# Master.net
KiCad netlist of a schematic drawn in EAGLE
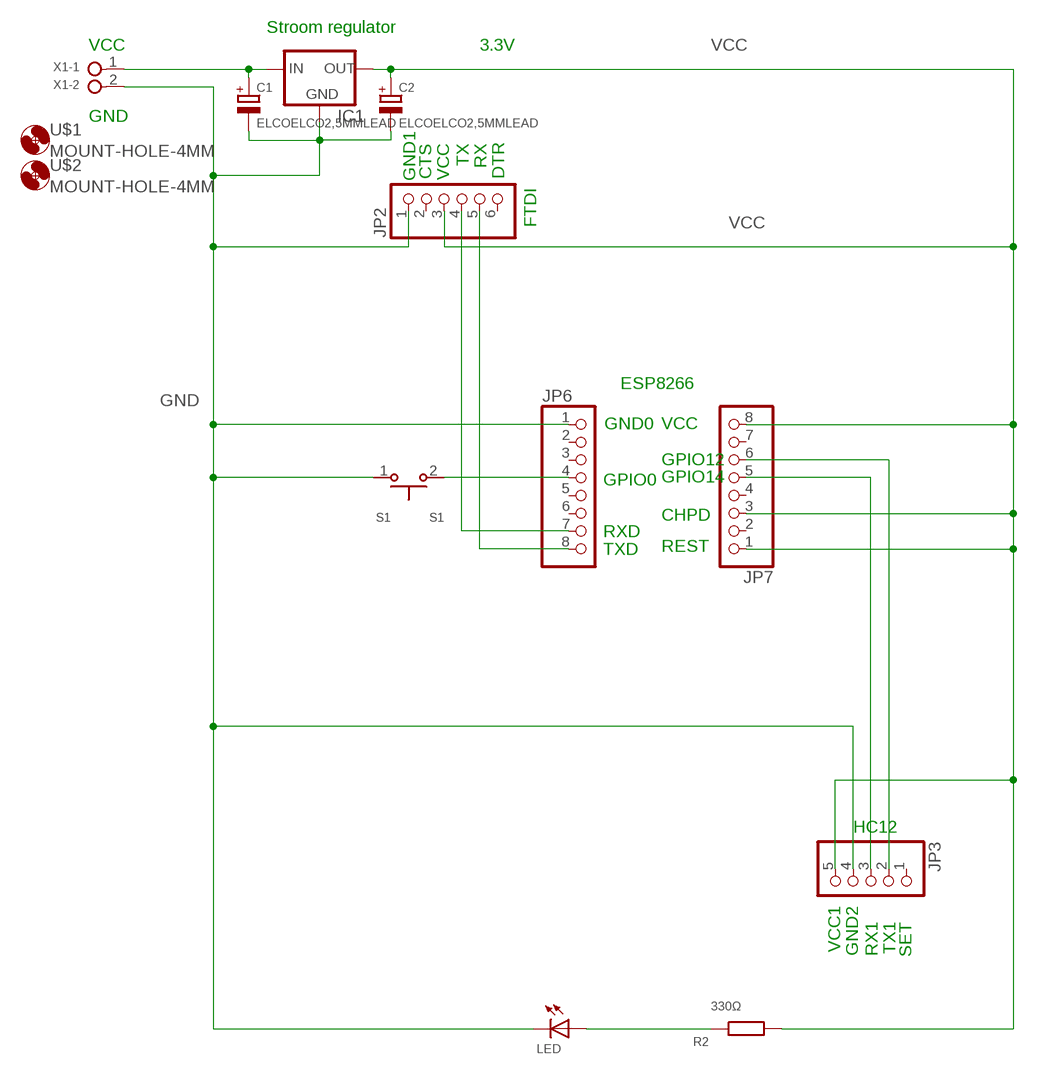
[diagram p0: schematic, sheet 1]

(export (version "E")
  (design (tool "Eeschema 10.0.6"))
  (components
    (comp (ref "C1")
      (value "ELCOELCO2,5MMLEAD")
      (footprint "eagle-import:ELCO-2.5MMLEAD")
      (libsource (lib "eagle-import") (part "ELCOELCO2,5MMLEAD"))
    )
    (comp (ref "C2")
      (value "ELCOELCO2,5MMLEAD")
      (footprint "eagle-import:ELCO-2.5MMLEAD")
      (libsource (lib "eagle-import") (part "ELCOELCO2,5MMLEAD"))
    )
    (comp (ref "IC1")
      (value "LM1117-TO220")
      (footprint "eagle-import:TO220V")
      (libsource (lib "eagle-import") (part "LM1117-TO220"))
    )
    (comp (ref "JP2")
      (value "PINHD-1X6")
      (footprint "eagle-import:1X06")
      (libsource (lib "eagle-import") (part "PINHD-1X6"))
    )
    (comp (ref "JP3")
      (value "PINHD-1X5")
      (footprint "eagle-import:1X05")
      (libsource (lib "eagle-import") (part "PINHD-1X5"))
    )
    (comp (ref "JP6")
      (value "PINHD-1X8")
      (footprint "eagle-import:1X08")
      (libsource (lib "eagle-import") (part "PINHD-1X8"))
    )
    (comp (ref "JP7")
      (value "PINHD-1X8")
      (footprint "eagle-import:1X08")
      (libsource (lib "eagle-import") (part "PINHD-1X8"))
    )
    (comp (ref "LED")
      (value "LED-SMD1206")
      (footprint "eagle-import:CHIPLED_1206")
      (libsource (lib "eagle-import") (part "LED-SMD1206"))
    )
    (comp (ref "R2")
      (value "330Ω")
      (footprint "eagle-import:R1206W")
      (libsource (lib "eagle-import") (part "RESISTOR-SMD-1206"))
    )
    (comp (ref "S1")
      (value "MICROSWITCH-B3U-1000P")
      (footprint "eagle-import:MICROSWITCH-B3U-1000P")
      (libsource (lib "eagle-import") (part "MICROSWITCH-B3U-1000P"))
    )
    (comp (ref "U$1")
      (value "MOUNT-HOLE-4MM")
      (footprint "eagle-import:4,0")
      (libsource (lib "eagle-import") (part "MOUNT-HOLE-4MM"))
    )
    (comp (ref "U$2")
      (value "MOUNT-HOLE-4MM")
      (footprint "eagle-import:4,0")
      (libsource (lib "eagle-import") (part "MOUNT-HOLE-4MM"))
    )
    (comp (ref "X1")
      (value "TERMINAL-5MM-2POLE")
      (footprint "eagle-import:W237-132")
      (libsource (lib "eagle-import") (part "TERMINAL-5MM-2POLE"))
    )
  )
  (nets
    (net (code "1") (name "/GND") (class "Default")
      (node (ref "C1") (pin "-") (pinfunction "-_-") (pintype "passive"))
      (node (ref "C2") (pin "-") (pinfunction "-_-") (pintype "passive"))
      (node (ref "IC1") (pin "1") (pinfunction "GND_1") (pintype "passive"))
      (node (ref "JP2") (pin "1") (pinfunction "1_1") (pintype "passive"))
      (node (ref "JP3") (pin "4") (pinfunction "4_4") (pintype "passive"))
      (node (ref "JP6") (pin "1") (pinfunction "1_1") (pintype "passive"))
      (node (ref "LED") (pin "C") (pinfunction "C_C") (pintype "passive"))
      (node (ref "S1") (pin "1") (pinfunction "P$1_1") (pintype "bidirectional"))
      (node (ref "X1") (pin "2") (pinfunction "P$2_2") (pintype "passive"))
    )
    (net (code "2") (name "/VCC") (class "Default")
      (node (ref "C2") (pin "+") (pinfunction "+_+") (pintype "passive"))
      (node (ref "IC1") (pin "2") (pinfunction "OUT_2") (pintype "passive"))
      (node (ref "JP2") (pin "3") (pinfunction "3_3") (pintype "passive"))
      (node (ref "JP3") (pin "5") (pinfunction "5_5") (pintype "passive"))
      (node (ref "JP7") (pin "1") (pinfunction "1_1") (pintype "passive"))
      (node (ref "JP7") (pin "3") (pinfunction "3_3") (pintype "passive"))
      (node (ref "JP7") (pin "8") (pinfunction "8_8") (pintype "passive"))
      (node (ref "R2") (pin "2") (pinfunction "2_2") (pintype "passive"))
    )
    (net (code "3") (name "Net-(IC1-IN)") (class "Default")
      (node (ref "C1") (pin "+") (pinfunction "+_+") (pintype "passive"))
      (node (ref "IC1") (pin "3") (pinfunction "IN_3") (pintype "passive"))
      (node (ref "X1") (pin "1") (pinfunction "P$1_1") (pintype "passive"))
    )
    (net (code "4") (name "Net-(JP2-Pad4)") (class "Default")
      (node (ref "JP2") (pin "4") (pinfunction "4_4") (pintype "passive"))
      (node (ref "JP6") (pin "7") (pinfunction "7_7") (pintype "passive"))
    )
    (net (code "5") (name "Net-(JP2-Pad5)") (class "Default")
      (node (ref "JP2") (pin "5") (pinfunction "5_5") (pintype "passive"))
      (node (ref "JP6") (pin "8") (pinfunction "8_8") (pintype "passive"))
    )
    (net (code "6") (name "Net-(JP3-Pad2)") (class "Default")
      (node (ref "JP3") (pin "2") (pinfunction "2_2") (pintype "passive"))
      (node (ref "JP7") (pin "6") (pinfunction "6_6") (pintype "passive"))
    )
    (net (code "7") (name "Net-(JP3-Pad3)") (class "Default")
      (node (ref "JP3") (pin "3") (pinfunction "3_3") (pintype "passive"))
      (node (ref "JP7") (pin "5") (pinfunction "5_5") (pintype "passive"))
    )
    (net (code "8") (name "Net-(LED-PadA)") (class "Default")
      (node (ref "LED") (pin "A") (pinfunction "A_A") (pintype "passive"))
      (node (ref "R2") (pin "1") (pinfunction "1_1") (pintype "passive"))
    )
    (net (code "9") (name "Net-(S1-P$2)") (class "Default")
      (node (ref "JP6") (pin "4") (pinfunction "4_4") (pintype "passive"))
      (node (ref "S1") (pin "2") (pinfunction "P$2_2") (pintype "bidirectional"))
    )
    (net (code "10") (name "unconnected-(JP2-Pad2)") (class "Default")
      (node (ref "JP2") (pin "2") (pinfunction "2_2") (pintype "passive"))
    )
    (net (code "11") (name "unconnected-(JP2-Pad6)") (class "Default")
      (node (ref "JP2") (pin "6") (pinfunction "6_6") (pintype "passive"))
    )
    (net (code "12") (name "unconnected-(JP3-Pad1)") (class "Default")
      (node (ref "JP3") (pin "1") (pinfunction "1_1") (pintype "passive"))
    )
    (net (code "13") (name "unconnected-(JP6-Pad2)") (class "Default")
      (node (ref "JP6") (pin "2") (pinfunction "2_2") (pintype "passive"))
    )
    (net (code "14") (name "unconnected-(JP6-Pad3)") (class "Default")
      (node (ref "JP6") (pin "3") (pinfunction "3_3") (pintype "passive"))
    )
    (net (code "15") (name "unconnected-(JP6-Pad5)") (class "Default")
      (node (ref "JP6") (pin "5") (pinfunction "5_5") (pintype "passive"))
    )
    (net (code "16") (name "unconnected-(JP6-Pad6)") (class "Default")
      (node (ref "JP6") (pin "6") (pinfunction "6_6") (pintype "passive"))
    )
    (net (code "17") (name "unconnected-(JP7-Pad2)") (class "Default")
      (node (ref "JP7") (pin "2") (pinfunction "2_2") (pintype "passive"))
    )
    (net (code "18") (name "unconnected-(JP7-Pad4)") (class "Default")
      (node (ref "JP7") (pin "4") (pinfunction "4_4") (pintype "passive"))
    )
    (net (code "19") (name "unconnected-(JP7-Pad7)") (class "Default")
      (node (ref "JP7") (pin "7") (pinfunction "7_7") (pintype "passive"))
    )
  )
)
